# SCH_lm386_amp_2024-08-24.net
KiCad netlist of a schematic drawn in EasyEDA
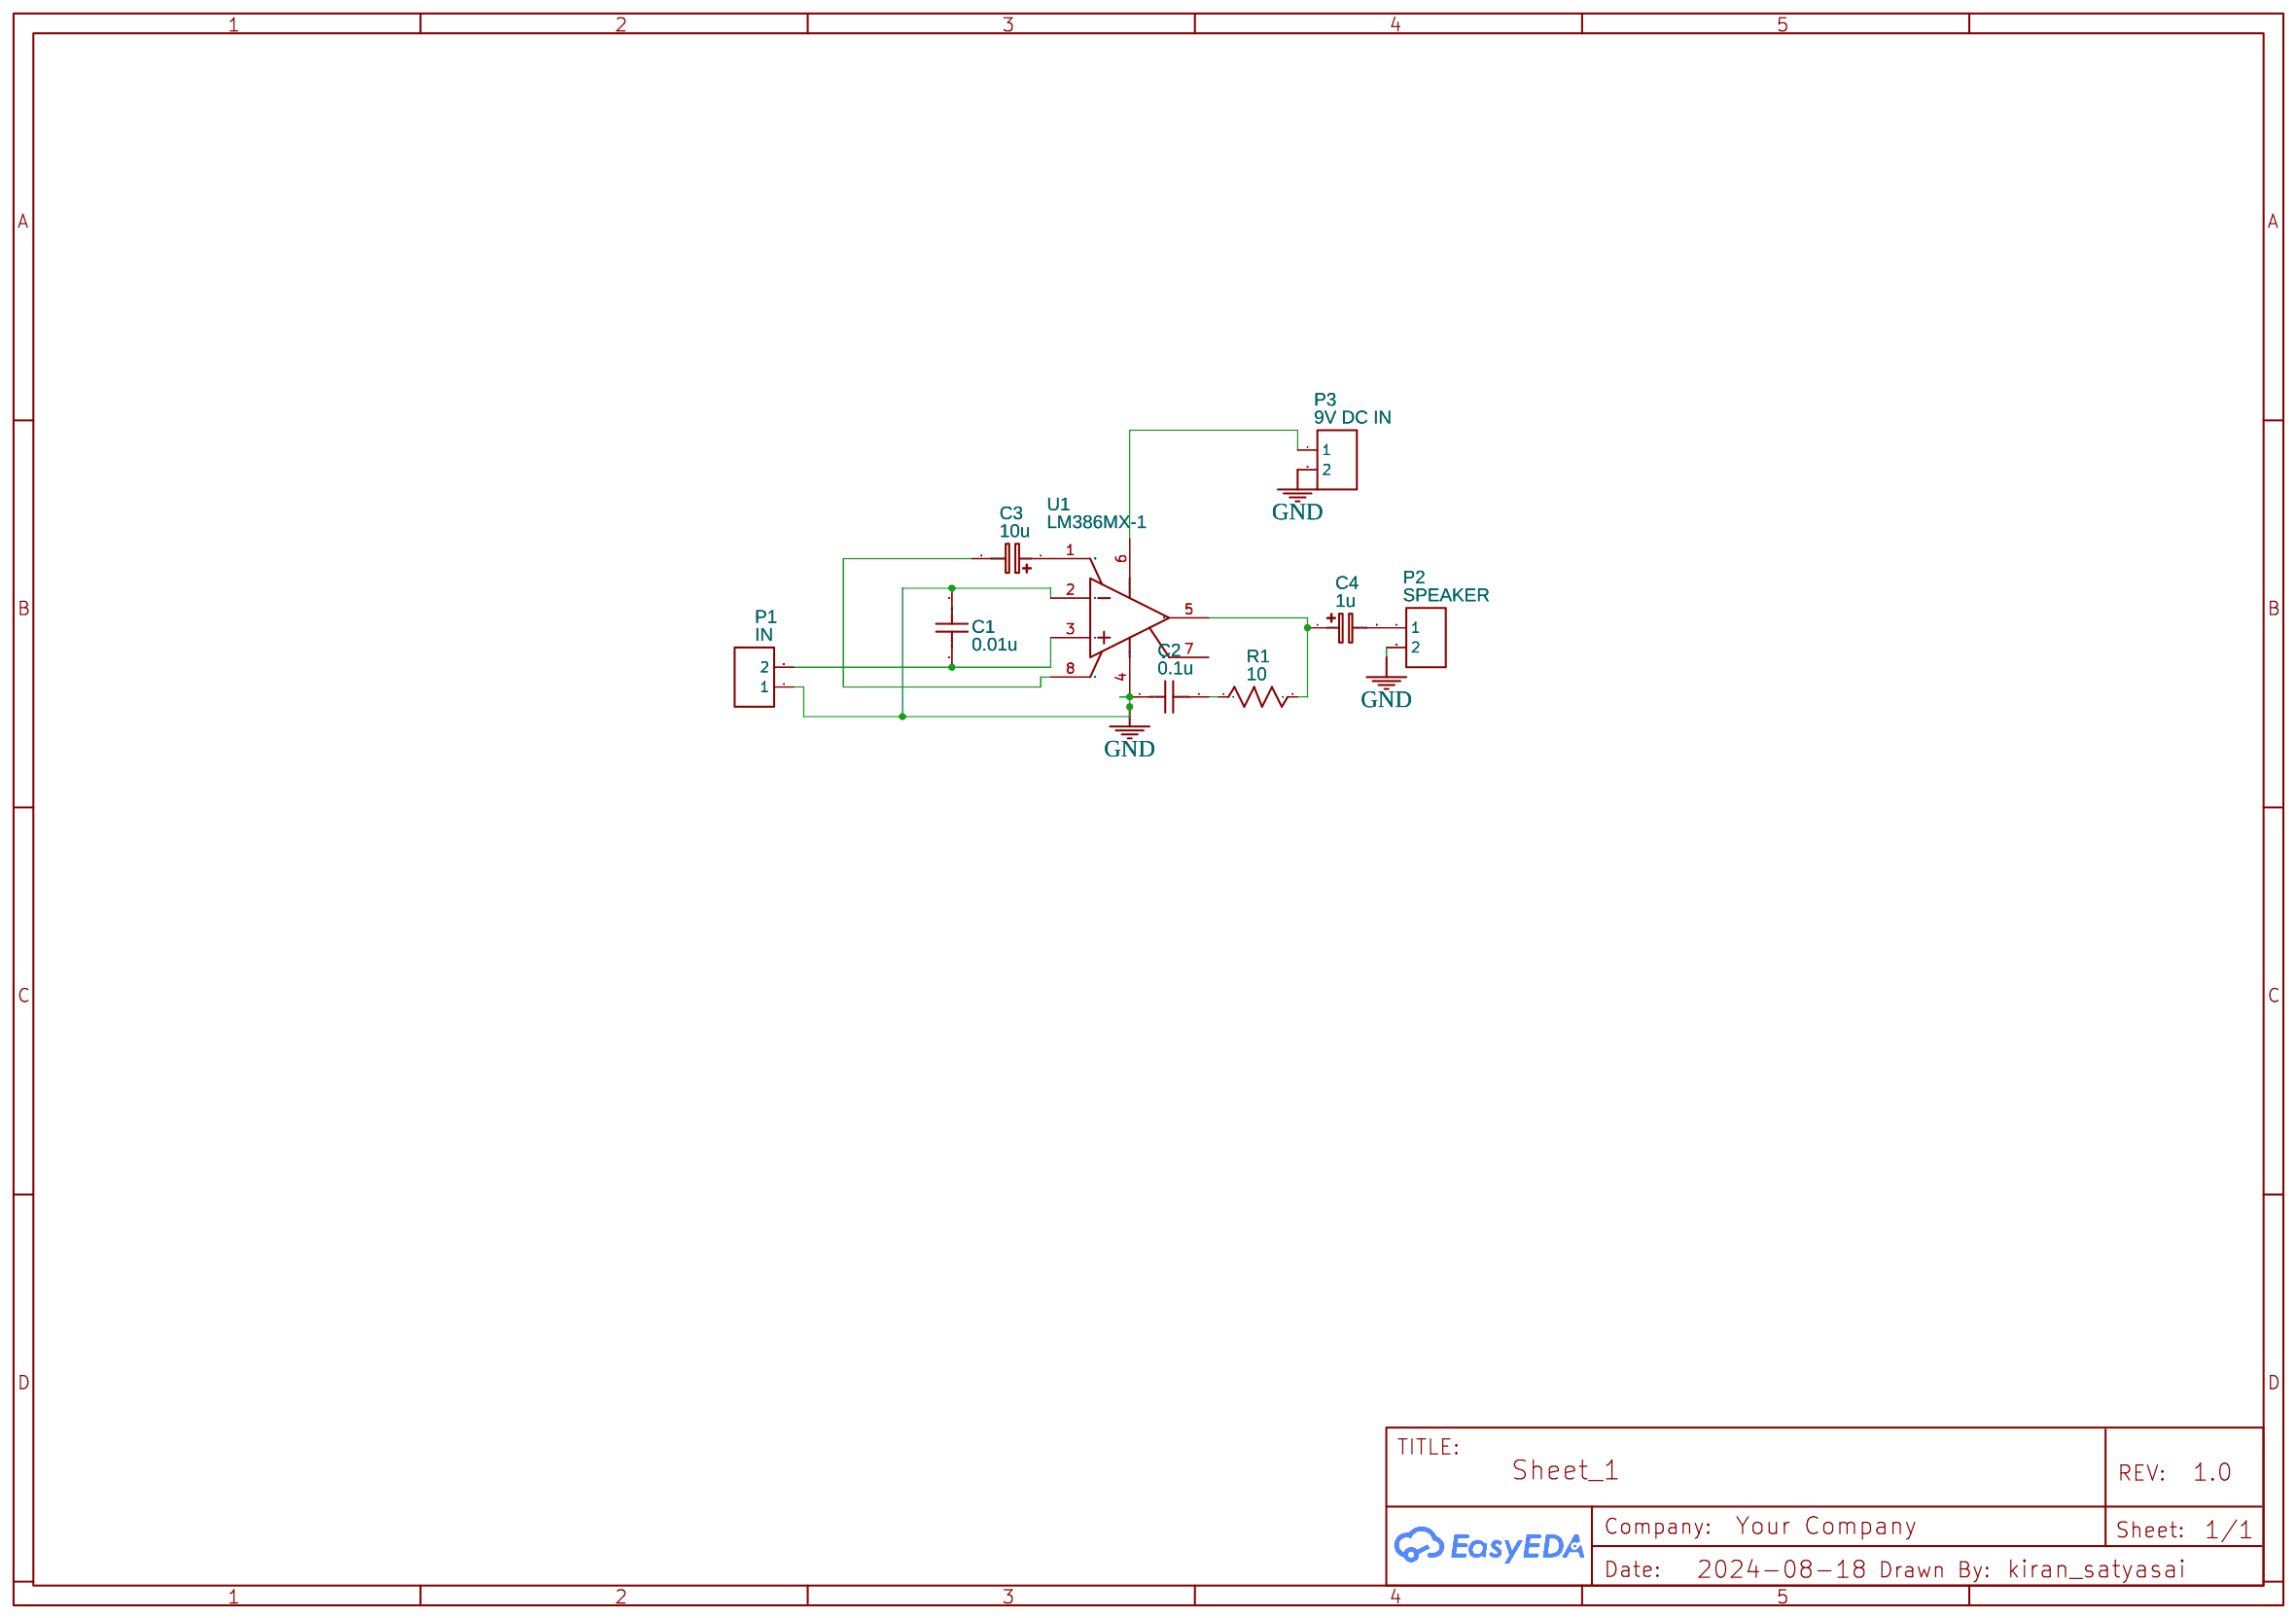
[diagram p0: schematic sheet]

(export (version "E")
  (design (tool "Eeschema 10.0.6"))
  (components
    (comp (ref "C1") (value "0.01u") (libsource (lib "") (part "C_0603_US")))
    (comp (ref "C2") (value "0.1u") (libsource (lib "") (part "C_0603_US_1")))
    (comp (ref "C3") (value "10u") (libsource (lib "") (part "C_Tan_SMD_A_EU")))
    (comp (ref "C4") (value "1u") (libsource (lib "") (part "C_Tan_SMD_A_EU_1")))
    (comp (ref "P1") (value "IN") (libsource (lib "") (part "CONN-TH_2P-P5.00_1")))
    (comp (ref "P2") (value "SPEAKER") (libsource (lib "") (part "CONN-TH_2P-P5.00")))
    (comp (ref "P3") (value "9V DC IN") (libsource (lib "") (part "CONN-TH_2P-P5.00")))
    (comp (ref "R1") (value "10") (libsource (lib "") (part "R_0603_US")))
    (comp (ref "U1")
      (value "LM386MX-1")
      (fields (field (name "Manufacturer") "TI(德州仪器)"))
      (libsource (lib "") (part "LM386MX-1"))
    )
  )
  (nets
    (net (code "1") (name "GND") (class "Default")
      (node (ref "C1") (pin "2") (pinfunction "2_2") (pintype "unspecified"))
      (node (ref "C2") (pin "1") (pinfunction "1_1") (pintype "unspecified"))
      (node (ref "P1") (pin "1") (pinfunction "1_1") (pintype "unspecified"))
      (node (ref "P2") (pin "2") (pinfunction "2_2") (pintype "unspecified"))
      (node (ref "P3") (pin "2") (pinfunction "2_2") (pintype "unspecified"))
      (node (ref "U1") (pin "2") (pinfunction "IN-_2") (pintype "unspecified"))
      (node (ref "U1") (pin "4") (pinfunction "GND_4") (pintype "passive"))
    )
    (net (code "2") (name "Net-(C2-Pad2)") (class "Default")
      (node (ref "C2") (pin "2") (pinfunction "2_2") (pintype "unspecified"))
      (node (ref "R1") (pin "1") (pinfunction "1_1") (pintype "unspecified"))
    )
    (net (code "3") (name "Net-(C3-Pad1)") (class "Default")
      (node (ref "C3") (pin "1") (pinfunction "1_1") (pintype "unspecified"))
      (node (ref "U1") (pin "1") (pinfunction "GAIN_1") (pintype "unspecified"))
    )
    (net (code "4") (name "Net-(C3-Pad2)") (class "Default")
      (node (ref "C3") (pin "2") (pinfunction "2_2") (pintype "unspecified"))
      (node (ref "U1") (pin "8") (pinfunction "GAIN_8") (pintype "unspecified"))
    )
    (net (code "5") (name "Net-(C4-Pad2)") (class "Default")
      (node (ref "C4") (pin "2") (pinfunction "2_2") (pintype "unspecified"))
      (node (ref "P2") (pin "1") (pinfunction "1_1") (pintype "unspecified"))
    )
    (net (code "6") (name "Net-(U1-IN+)") (class "Default")
      (node (ref "C1") (pin "1") (pinfunction "1_1") (pintype "unspecified"))
      (node (ref "P1") (pin "2") (pinfunction "2_2") (pintype "unspecified"))
      (node (ref "U1") (pin "3") (pinfunction "IN+_3") (pintype "unspecified"))
    )
    (net (code "7") (name "Net-(U1-VOUT)") (class "Default")
      (node (ref "C4") (pin "1") (pinfunction "1_1") (pintype "unspecified"))
      (node (ref "R1") (pin "2") (pinfunction "2_2") (pintype "unspecified"))
      (node (ref "U1") (pin "5") (pinfunction "VOUT_5") (pintype "output"))
    )
    (net (code "8") (name "Net-(U1-VS)") (class "Default")
      (node (ref "P3") (pin "1") (pinfunction "1_1") (pintype "unspecified"))
      (node (ref "U1") (pin "6") (pinfunction "VS_6") (pintype "passive"))
    )
    (net (code "9") (name "unconnected-(U1-BYPASS-Pad7)") (class "Default")
      (node (ref "U1") (pin "7") (pinfunction "BYPASS_7") (pintype "unspecified"))
    )
  )
)
